# CubeBoard.net
KiCad netlist of a schematic drawn in EAGLE
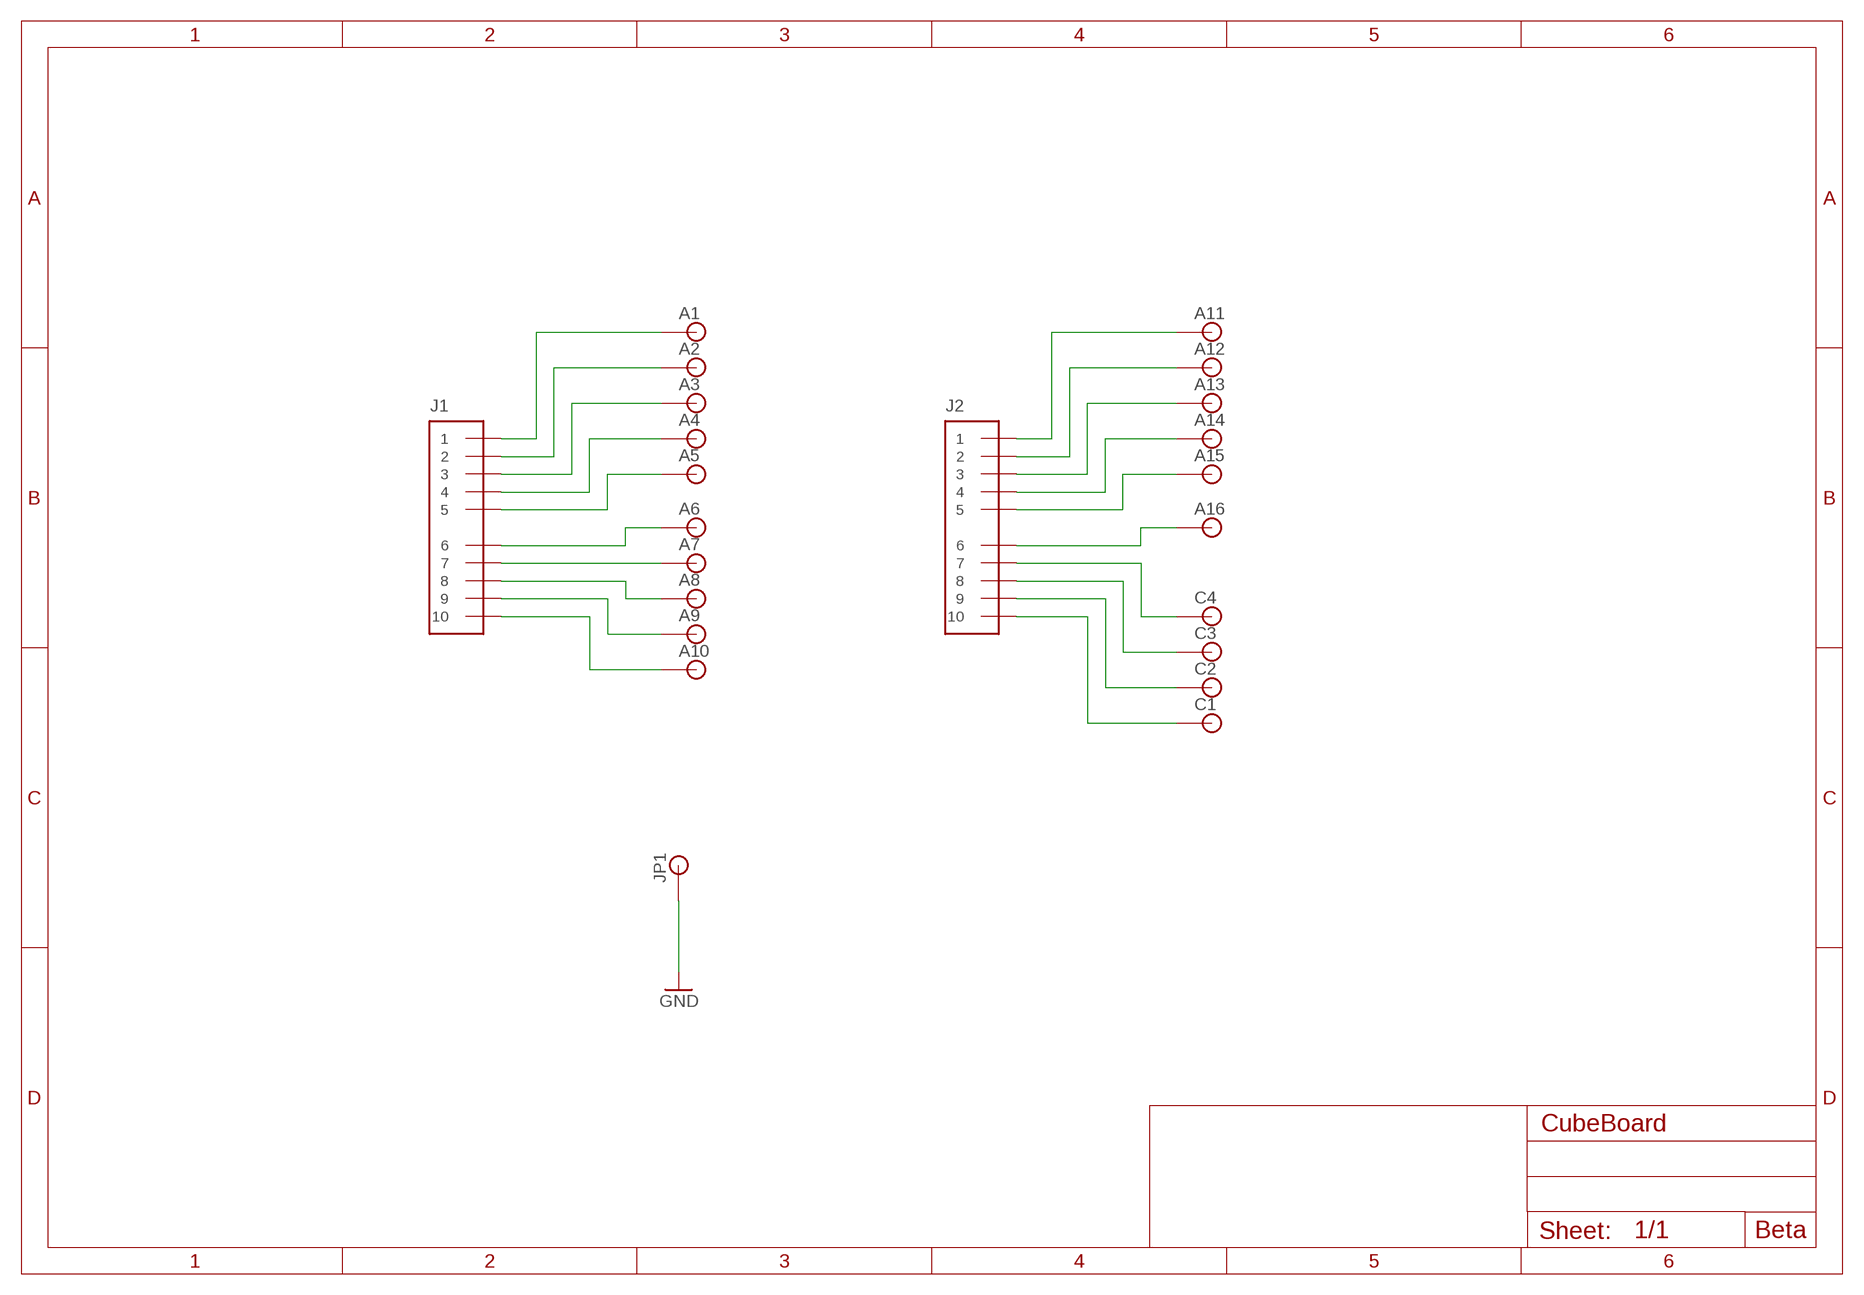
[diagram p0: schematic, sheet 1]

(export (version "E")
  (design (tool "Eeschema 10.0.6"))
  (components
    (comp (ref "A1")
      (value "anode1")
      (footprint "eagle-import:PIN-1X1")
      (libsource (lib "eagle-import") (part "PIN-1X1"))
    )
    (comp (ref "A2")
      (value "anode2")
      (footprint "eagle-import:PIN-1X1")
      (libsource (lib "eagle-import") (part "PIN-1X1"))
    )
    (comp (ref "A3")
      (value "anode3")
      (footprint "eagle-import:PIN-1X1")
      (libsource (lib "eagle-import") (part "PIN-1X1"))
    )
    (comp (ref "A4")
      (value "anode4")
      (footprint "eagle-import:PIN-1X1")
      (libsource (lib "eagle-import") (part "PIN-1X1"))
    )
    (comp (ref "A5")
      (value "anode5")
      (footprint "eagle-import:PIN-1X1")
      (libsource (lib "eagle-import") (part "PIN-1X1"))
    )
    (comp (ref "A6")
      (value "anode6")
      (footprint "eagle-import:PIN-1X1")
      (libsource (lib "eagle-import") (part "PIN-1X1"))
    )
    (comp (ref "A7")
      (value "anode7")
      (footprint "eagle-import:PIN-1X1")
      (libsource (lib "eagle-import") (part "PIN-1X1"))
    )
    (comp (ref "A8")
      (value "anode8")
      (footprint "eagle-import:PIN-1X1")
      (libsource (lib "eagle-import") (part "PIN-1X1"))
    )
    (comp (ref "A9")
      (value "anode9")
      (footprint "eagle-import:PIN-1X1")
      (libsource (lib "eagle-import") (part "PIN-1X1"))
    )
    (comp (ref "A10")
      (value "anode10")
      (footprint "eagle-import:PIN-1X1")
      (libsource (lib "eagle-import") (part "PIN-1X1"))
    )
    (comp (ref "A11")
      (value "anode11")
      (footprint "eagle-import:PIN-1X1")
      (libsource (lib "eagle-import") (part "PIN-1X1"))
    )
    (comp (ref "A12")
      (value "anode12")
      (footprint "eagle-import:PIN-1X1")
      (libsource (lib "eagle-import") (part "PIN-1X1"))
    )
    (comp (ref "A13")
      (value "anode13")
      (footprint "eagle-import:PIN-1X1")
      (libsource (lib "eagle-import") (part "PIN-1X1"))
    )
    (comp (ref "A14")
      (value "anode14")
      (footprint "eagle-import:PIN-1X1")
      (libsource (lib "eagle-import") (part "PIN-1X1"))
    )
    (comp (ref "A15")
      (value "anode15")
      (footprint "eagle-import:PIN-1X1")
      (libsource (lib "eagle-import") (part "PIN-1X1"))
    )
    (comp (ref "A16")
      (value "anode16")
      (footprint "eagle-import:PIN-1X1")
      (libsource (lib "eagle-import") (part "PIN-1X1"))
    )
    (comp (ref "C1")
      (value "cathode1")
      (footprint "eagle-import:PIN-1X1")
      (libsource (lib "eagle-import") (part "PIN-1X1"))
    )
    (comp (ref "C2")
      (value "cathode2")
      (footprint "eagle-import:PIN-1X1")
      (libsource (lib "eagle-import") (part "PIN-1X1"))
    )
    (comp (ref "C3")
      (value "cathode3")
      (footprint "eagle-import:PIN-1X1")
      (libsource (lib "eagle-import") (part "PIN-1X1"))
    )
    (comp (ref "C4")
      (value "cathode4")
      (footprint "eagle-import:PIN-1X1")
      (libsource (lib "eagle-import") (part "PIN-1X1"))
    )
    (comp (ref "J1")
      (value "PINHEAD-1X10")
      (footprint "eagle-import:1X10-SNEAKY")
      (libsource (lib "eagle-import") (part "PINHEAD-1X10"))
    )
    (comp (ref "J2")
      (value "PINHEAD-1X10")
      (footprint "eagle-import:1X10-SNEAKY")
      (libsource (lib "eagle-import") (part "PINHEAD-1X10"))
    )
    (comp (ref "JP1")
      (value "PIN-1X1")
      (footprint "eagle-import:PIN-1X1")
      (libsource (lib "eagle-import") (part "PIN-1X1"))
    )
  )
  (nets
    (net (code "1") (name "GND") (class "Default")
      (node (ref "JP1") (pin "1") (pinfunction "1_1") (pintype "bidirectional"))
    )
    (net (code "2") (name "Net-(A1-Pad1)") (class "Default")
      (node (ref "A1") (pin "1") (pinfunction "1_1") (pintype "bidirectional"))
      (node (ref "J1") (pin "1") (pinfunction "1_1") (pintype "bidirectional"))
    )
    (net (code "3") (name "Net-(A2-Pad1)") (class "Default")
      (node (ref "A2") (pin "1") (pinfunction "1_1") (pintype "bidirectional"))
      (node (ref "J1") (pin "2") (pinfunction "2_2") (pintype "bidirectional"))
    )
    (net (code "4") (name "Net-(A3-Pad1)") (class "Default")
      (node (ref "A3") (pin "1") (pinfunction "1_1") (pintype "bidirectional"))
      (node (ref "J1") (pin "3") (pinfunction "3_3") (pintype "bidirectional"))
    )
    (net (code "5") (name "Net-(A4-Pad1)") (class "Default")
      (node (ref "A4") (pin "1") (pinfunction "1_1") (pintype "bidirectional"))
      (node (ref "J1") (pin "4") (pinfunction "4_4") (pintype "bidirectional"))
    )
    (net (code "6") (name "Net-(A5-Pad1)") (class "Default")
      (node (ref "A5") (pin "1") (pinfunction "1_1") (pintype "bidirectional"))
      (node (ref "J1") (pin "5") (pinfunction "5_5") (pintype "bidirectional"))
    )
    (net (code "7") (name "Net-(A6-Pad1)") (class "Default")
      (node (ref "A6") (pin "1") (pinfunction "1_1") (pintype "bidirectional"))
      (node (ref "J1") (pin "6") (pinfunction "6_6") (pintype "bidirectional"))
    )
    (net (code "8") (name "Net-(A7-Pad1)") (class "Default")
      (node (ref "A7") (pin "1") (pinfunction "1_1") (pintype "bidirectional"))
      (node (ref "J1") (pin "7") (pinfunction "7_7") (pintype "bidirectional"))
    )
    (net (code "9") (name "Net-(A8-Pad1)") (class "Default")
      (node (ref "A8") (pin "1") (pinfunction "1_1") (pintype "bidirectional"))
      (node (ref "J1") (pin "8") (pinfunction "8_8") (pintype "bidirectional"))
    )
    (net (code "10") (name "Net-(A9-Pad1)") (class "Default")
      (node (ref "A9") (pin "1") (pinfunction "1_1") (pintype "bidirectional"))
      (node (ref "J1") (pin "9") (pinfunction "9_9") (pintype "bidirectional"))
    )
    (net (code "11") (name "Net-(A10-Pad1)") (class "Default")
      (node (ref "A10") (pin "1") (pinfunction "1_1") (pintype "bidirectional"))
      (node (ref "J1") (pin "10") (pinfunction "10_10") (pintype "bidirectional"))
    )
    (net (code "12") (name "Net-(A11-Pad1)") (class "Default")
      (node (ref "A11") (pin "1") (pinfunction "1_1") (pintype "bidirectional"))
      (node (ref "J2") (pin "1") (pinfunction "1_1") (pintype "bidirectional"))
    )
    (net (code "13") (name "Net-(A12-Pad1)") (class "Default")
      (node (ref "A12") (pin "1") (pinfunction "1_1") (pintype "bidirectional"))
      (node (ref "J2") (pin "2") (pinfunction "2_2") (pintype "bidirectional"))
    )
    (net (code "14") (name "Net-(A13-Pad1)") (class "Default")
      (node (ref "A13") (pin "1") (pinfunction "1_1") (pintype "bidirectional"))
      (node (ref "J2") (pin "3") (pinfunction "3_3") (pintype "bidirectional"))
    )
    (net (code "15") (name "Net-(A14-Pad1)") (class "Default")
      (node (ref "A14") (pin "1") (pinfunction "1_1") (pintype "bidirectional"))
      (node (ref "J2") (pin "4") (pinfunction "4_4") (pintype "bidirectional"))
    )
    (net (code "16") (name "Net-(A15-Pad1)") (class "Default")
      (node (ref "A15") (pin "1") (pinfunction "1_1") (pintype "bidirectional"))
      (node (ref "J2") (pin "5") (pinfunction "5_5") (pintype "bidirectional"))
    )
    (net (code "17") (name "Net-(A16-Pad1)") (class "Default")
      (node (ref "A16") (pin "1") (pinfunction "1_1") (pintype "bidirectional"))
      (node (ref "J2") (pin "6") (pinfunction "6_6") (pintype "bidirectional"))
    )
    (net (code "18") (name "Net-(C1-Pad1)") (class "Default")
      (node (ref "C1") (pin "1") (pinfunction "1_1") (pintype "bidirectional"))
      (node (ref "J2") (pin "10") (pinfunction "10_10") (pintype "bidirectional"))
    )
    (net (code "19") (name "Net-(C2-Pad1)") (class "Default")
      (node (ref "C2") (pin "1") (pinfunction "1_1") (pintype "bidirectional"))
      (node (ref "J2") (pin "9") (pinfunction "9_9") (pintype "bidirectional"))
    )
    (net (code "20") (name "Net-(C3-Pad1)") (class "Default")
      (node (ref "C3") (pin "1") (pinfunction "1_1") (pintype "bidirectional"))
      (node (ref "J2") (pin "8") (pinfunction "8_8") (pintype "bidirectional"))
    )
    (net (code "21") (name "Net-(C4-Pad1)") (class "Default")
      (node (ref "C4") (pin "1") (pinfunction "1_1") (pintype "bidirectional"))
      (node (ref "J2") (pin "7") (pinfunction "7_7") (pintype "bidirectional"))
    )
  )
)
